# Board.net
KiCad netlist of a schematic drawn in EAGLE
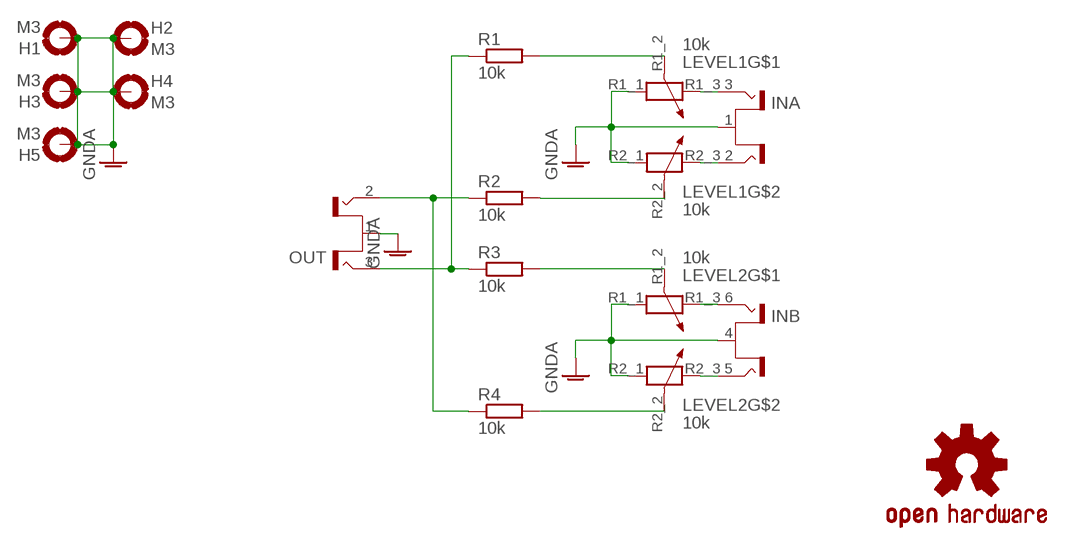
[diagram p0: schematic, sheet 1]

(export (version "E")
  (design (tool "Eeschema 10.0.6"))
  (components
    (comp (ref "H1")
      (value "M3")
      (footprint "eagle-import:3,0-PAD")
      (libsource (lib "eagle-import") (part "MOUNT-PAD-ROUND3.0"))
    )
    (comp (ref "H2")
      (value "M3")
      (footprint "eagle-import:3,0-PAD")
      (libsource (lib "eagle-import") (part "MOUNT-PAD-ROUND3.0"))
    )
    (comp (ref "H3")
      (value "M3")
      (footprint "eagle-import:3,0-PAD")
      (libsource (lib "eagle-import") (part "MOUNT-PAD-ROUND3.0"))
    )
    (comp (ref "H4")
      (value "M3")
      (footprint "eagle-import:3,0-PAD")
      (libsource (lib "eagle-import") (part "MOUNT-PAD-ROUND3.0"))
    )
    (comp (ref "H5")
      (value "M3")
      (footprint "eagle-import:3,0-PAD")
      (libsource (lib "eagle-import") (part "MOUNT-PAD-ROUND3.0"))
    )
    (comp (ref "IN")
      (value "RCA-4-117-01")
      (footprint "eagle-import:RCA-4-117-01")
      (libsource (lib "eagle-import") (part "RCA-4-117-01"))
    )
    (comp (ref "LEVEL1")
      (value "10k")
      (footprint "eagle-import:ALPS-RK09L12B0")
      (libsource (lib "eagle-import") (part "ALPS-RK09L12B0"))
    )
    (comp (ref "LEVEL2")
      (value "10k")
      (footprint "eagle-import:ALPS-RK09L12B0")
      (libsource (lib "eagle-import") (part "ALPS-RK09L12B0"))
    )
    (comp (ref "LOGO1")
      (value "OSHW-LOGOL-COPPER")
      (footprint "eagle-import:OSHW-LOGO-L_COPPER")
      (libsource (lib "eagle-import") (part "OSHW-LOGOL-COPPER"))
    )
    (comp (ref "OUT")
      (value "RCA-2-117-01")
      (footprint "eagle-import:RCA-2-117-01")
      (libsource (lib "eagle-import") (part "RCA-2-117-01"))
    )
    (comp (ref "R1")
      (value "10k")
      (footprint "eagle-import:0414_15")
      (libsource (lib "eagle-import") (part "R-EU_0414/15"))
    )
    (comp (ref "R2")
      (value "10k")
      (footprint "eagle-import:0414_15")
      (libsource (lib "eagle-import") (part "R-EU_0414/15"))
    )
    (comp (ref "R3")
      (value "10k")
      (footprint "eagle-import:0414_15")
      (libsource (lib "eagle-import") (part "R-EU_0414/15"))
    )
    (comp (ref "R4")
      (value "10k")
      (footprint "eagle-import:0414_15")
      (libsource (lib "eagle-import") (part "R-EU_0414/15"))
    )
  )
  (nets
    (net (code "1") (name "GNDA") (class "Default")
      (node (ref "H1") (pin "B3,0") (pinfunction "MOUNT_B3,0") (pintype "passive"))
      (node (ref "H2") (pin "B3,0") (pinfunction "MOUNT_B3,0") (pintype "passive"))
      (node (ref "H3") (pin "B3,0") (pinfunction "MOUNT_B3,0") (pintype "passive"))
      (node (ref "H4") (pin "B3,0") (pinfunction "MOUNT_B3,0") (pintype "passive"))
      (node (ref "H5") (pin "B3,0") (pinfunction "MOUNT_B3,0") (pintype "passive"))
      (node (ref "IN") (pin "1") (pinfunction "S_1") (pintype "passive"))
      (node (ref "IN") (pin "4") (pinfunction "S_4") (pintype "passive"))
      (node (ref "LEVEL1") (pin "R1_1") (pinfunction "1_R1_1") (pintype "passive"))
      (node (ref "LEVEL1") (pin "R2_1") (pinfunction "1_R2_1") (pintype "passive"))
      (node (ref "LEVEL2") (pin "R1_1") (pinfunction "1_R1_1") (pintype "passive"))
      (node (ref "LEVEL2") (pin "R2_1") (pinfunction "1_R2_1") (pintype "passive"))
      (node (ref "OUT") (pin "1") (pinfunction "S_1") (pintype "passive"))
    )
    (net (code "2") (name "Net-(INA-T1)") (class "Default")
      (node (ref "IN") (pin "2") (pinfunction "T1_2") (pintype "passive"))
      (node (ref "LEVEL1") (pin "R2_3") (pinfunction "2_R2_3") (pintype "passive"))
    )
    (net (code "3") (name "Net-(INA-T2)") (class "Default")
      (node (ref "IN") (pin "3") (pinfunction "T2_3") (pintype "passive"))
      (node (ref "LEVEL1") (pin "R1_3") (pinfunction "2_R1_3") (pintype "passive"))
    )
    (net (code "4") (name "Net-(INB-T1)") (class "Default")
      (node (ref "IN") (pin "5") (pinfunction "T1_5") (pintype "passive"))
      (node (ref "LEVEL2") (pin "R2_3") (pinfunction "2_R2_3") (pintype "passive"))
    )
    (net (code "5") (name "Net-(INB-T2)") (class "Default")
      (node (ref "IN") (pin "6") (pinfunction "T2_6") (pintype "passive"))
      (node (ref "LEVEL2") (pin "R1_3") (pinfunction "2_R1_3") (pintype "passive"))
    )
    (net (code "6") (name "Net-(LEVEL1A-3)") (class "Default")
      (node (ref "LEVEL1") (pin "R1_2") (pinfunction "3_R1_2") (pintype "passive"))
      (node (ref "R1") (pin "2") (pinfunction "2_2") (pintype "passive"))
    )
    (net (code "7") (name "Net-(LEVEL1B-3)") (class "Default")
      (node (ref "LEVEL1") (pin "R2_2") (pinfunction "3_R2_2") (pintype "passive"))
      (node (ref "R2") (pin "2") (pinfunction "2_2") (pintype "passive"))
    )
    (net (code "8") (name "Net-(LEVEL2A-3)") (class "Default")
      (node (ref "LEVEL2") (pin "R1_2") (pinfunction "3_R1_2") (pintype "passive"))
      (node (ref "R3") (pin "2") (pinfunction "2_2") (pintype "passive"))
    )
    (net (code "9") (name "Net-(LEVEL2B-3)") (class "Default")
      (node (ref "LEVEL2") (pin "R2_2") (pinfunction "3_R2_2") (pintype "passive"))
      (node (ref "R4") (pin "2") (pinfunction "2_2") (pintype "passive"))
    )
    (net (code "10") (name "Net-(OUT-T1)") (class "Default")
      (node (ref "OUT") (pin "2") (pinfunction "T1_2") (pintype "passive"))
      (node (ref "R2") (pin "1") (pinfunction "1_1") (pintype "passive"))
      (node (ref "R4") (pin "1") (pinfunction "1_1") (pintype "passive"))
    )
    (net (code "11") (name "Net-(OUT-T2)") (class "Default")
      (node (ref "OUT") (pin "3") (pinfunction "T2_3") (pintype "passive"))
      (node (ref "R1") (pin "1") (pinfunction "1_1") (pintype "passive"))
      (node (ref "R3") (pin "1") (pinfunction "1_1") (pintype "passive"))
    )
  )
)
